# Xonik_Waveformer_v1_0.net
KiCad netlist of a schematic drawn in EAGLE
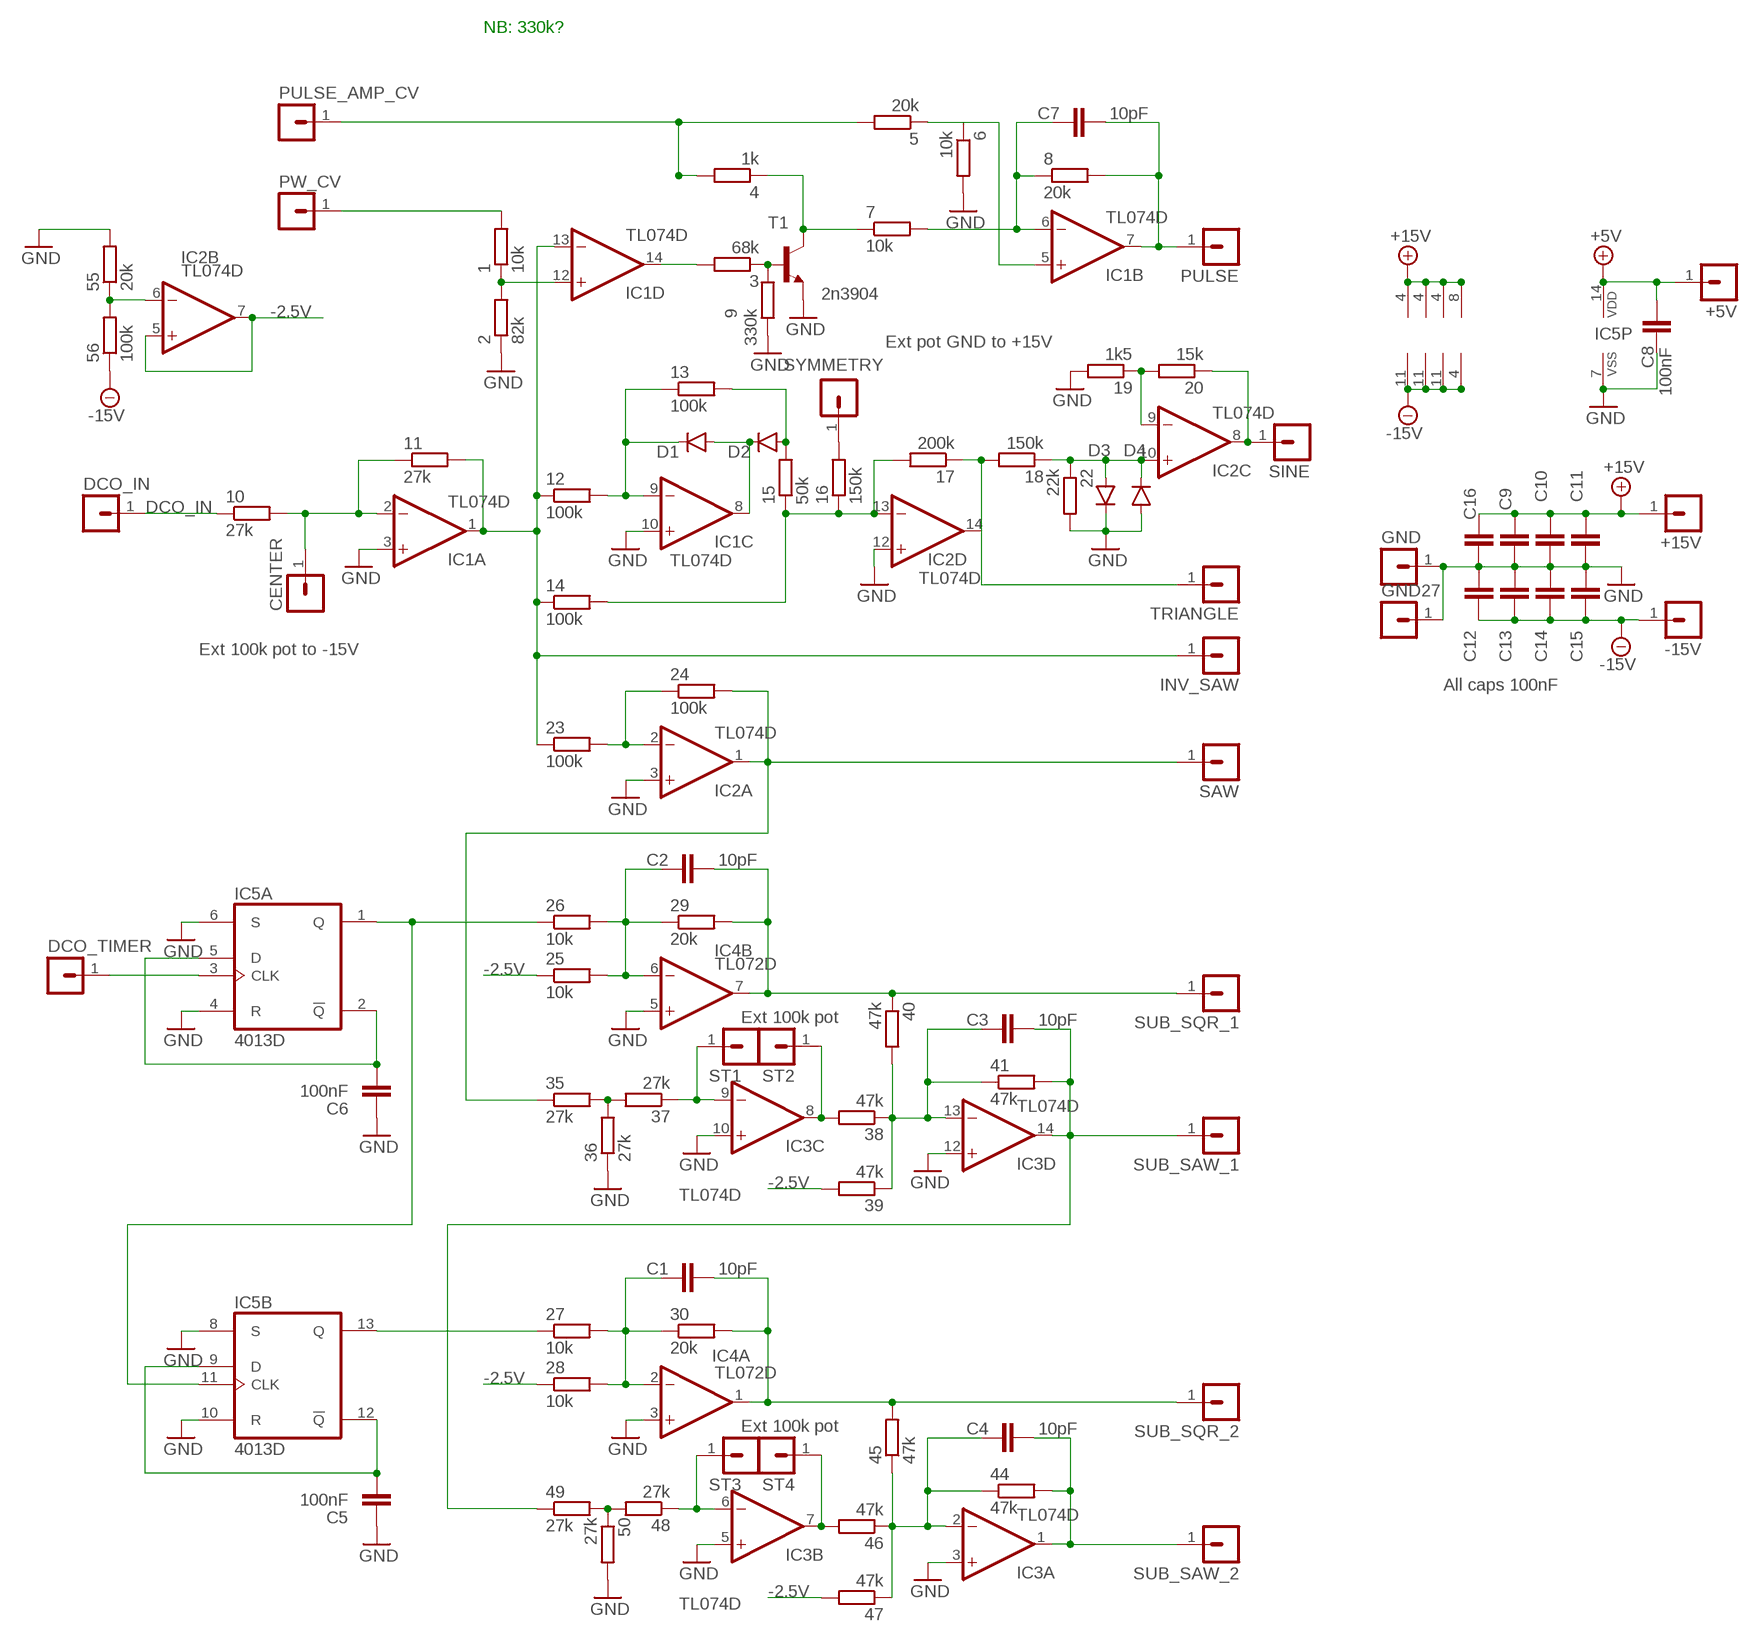
[diagram p0: schematic, sheet 1]

(export (version "E")
  (design (tool "Eeschema 10.0.6"))
  (components
    (comp (ref "+5V")
      (value "MA01-1JP")
      (footprint "eagle-import:SIP-PIN01-1J")
      (libsource (lib "eagle-import") (part "MA01-1JP"))
    )
    (comp (ref "+15V")
      (value "MA01-1JP")
      (footprint "eagle-import:SIP-PIN01-1J")
      (libsource (lib "eagle-import") (part "MA01-1JP"))
    )
    (comp (ref "-15V")
      (value "MA01-1JP")
      (footprint "eagle-import:SIP-PIN01-1J")
      (libsource (lib "eagle-import") (part "MA01-1JP"))
    )
    (comp (ref "1")
      (value "10k")
      (footprint "eagle-import:R0805")
      (libsource (lib "eagle-import") (part "R-EU_R0805"))
    )
    (comp (ref "2")
      (value "82k")
      (footprint "eagle-import:R0805")
      (libsource (lib "eagle-import") (part "R-EU_R0805"))
    )
    (comp (ref "3")
      (value "68k")
      (footprint "eagle-import:R0805")
      (libsource (lib "eagle-import") (part "R-EU_R0805"))
    )
    (comp (ref "4")
      (value "1k")
      (footprint "eagle-import:R0805")
      (libsource (lib "eagle-import") (part "R-EU_R0805"))
    )
    (comp (ref "5")
      (value "20k")
      (footprint "eagle-import:R0805")
      (libsource (lib "eagle-import") (part "R-EU_R0805"))
    )
    (comp (ref "6")
      (value "10k")
      (footprint "eagle-import:R0805")
      (libsource (lib "eagle-import") (part "R-EU_R0805"))
    )
    (comp (ref "7")
      (value "10k")
      (footprint "eagle-import:R0805")
      (libsource (lib "eagle-import") (part "R-EU_R0805"))
    )
    (comp (ref "8")
      (value "20k")
      (footprint "eagle-import:R0805")
      (libsource (lib "eagle-import") (part "R-EU_R0805"))
    )
    (comp (ref "9")
      (value "330k")
      (footprint "eagle-import:R0805")
      (libsource (lib "eagle-import") (part "R-EU_R0805"))
    )
    (comp (ref "10")
      (value "27k")
      (footprint "eagle-import:R0805")
      (libsource (lib "eagle-import") (part "R-EU_R0805"))
    )
    (comp (ref "11")
      (value "27k")
      (footprint "eagle-import:R0805")
      (libsource (lib "eagle-import") (part "R-EU_R0805"))
    )
    (comp (ref "12")
      (value "100k")
      (footprint "eagle-import:R0805")
      (libsource (lib "eagle-import") (part "R-EU_R0805"))
    )
    (comp (ref "13")
      (value "100k")
      (footprint "eagle-import:R0805")
      (libsource (lib "eagle-import") (part "R-EU_R0805"))
    )
    (comp (ref "14")
      (value "100k")
      (footprint "eagle-import:R0805")
      (libsource (lib "eagle-import") (part "R-EU_R0805"))
    )
    (comp (ref "15")
      (value "50k")
      (footprint "eagle-import:R0805")
      (libsource (lib "eagle-import") (part "R-EU_R0805"))
    )
    (comp (ref "16")
      (value "150k")
      (footprint "eagle-import:R0805")
      (libsource (lib "eagle-import") (part "R-EU_R0805"))
    )
    (comp (ref "17")
      (value "200k")
      (footprint "eagle-import:R0805")
      (libsource (lib "eagle-import") (part "R-EU_R0805"))
    )
    (comp (ref "18")
      (value "150k")
      (footprint "eagle-import:R0805")
      (libsource (lib "eagle-import") (part "R-EU_R0805"))
    )
    (comp (ref "19")
      (value "1k5")
      (footprint "eagle-import:R0805")
      (libsource (lib "eagle-import") (part "R-EU_R0805"))
    )
    (comp (ref "20")
      (value "15k")
      (footprint "eagle-import:R0805")
      (libsource (lib "eagle-import") (part "R-EU_R0805"))
    )
    (comp (ref "22")
      (value "22k")
      (footprint "eagle-import:R0805")
      (libsource (lib "eagle-import") (part "R-EU_R0805"))
    )
    (comp (ref "23")
      (value "100k")
      (footprint "eagle-import:R0805")
      (libsource (lib "eagle-import") (part "R-EU_R0805"))
    )
    (comp (ref "24")
      (value "100k")
      (footprint "eagle-import:R0805")
      (libsource (lib "eagle-import") (part "R-EU_R0805"))
    )
    (comp (ref "25")
      (value "10k")
      (footprint "eagle-import:R0805")
      (libsource (lib "eagle-import") (part "R-EU_R0805"))
    )
    (comp (ref "26")
      (value "10k")
      (footprint "eagle-import:R0805")
      (libsource (lib "eagle-import") (part "R-EU_R0805"))
    )
    (comp (ref "27")
      (value "10k")
      (footprint "eagle-import:R0805")
      (libsource (lib "eagle-import") (part "R-EU_R0805"))
    )
    (comp (ref "28")
      (value "10k")
      (footprint "eagle-import:R0805")
      (libsource (lib "eagle-import") (part "R-EU_R0805"))
    )
    (comp (ref "29")
      (value "20k")
      (footprint "eagle-import:R0805")
      (libsource (lib "eagle-import") (part "R-EU_R0805"))
    )
    (comp (ref "30")
      (value "20k")
      (footprint "eagle-import:R0805")
      (libsource (lib "eagle-import") (part "R-EU_R0805"))
    )
    (comp (ref "35")
      (value "27k")
      (footprint "eagle-import:R0805")
      (libsource (lib "eagle-import") (part "R-EU_R0805"))
    )
    (comp (ref "36")
      (value "27k")
      (footprint "eagle-import:R0805")
      (libsource (lib "eagle-import") (part "R-EU_R0805"))
    )
    (comp (ref "37")
      (value "27k")
      (footprint "eagle-import:R0805")
      (libsource (lib "eagle-import") (part "R-EU_R0805"))
    )
    (comp (ref "38")
      (value "47k")
      (footprint "eagle-import:R0805")
      (libsource (lib "eagle-import") (part "R-EU_R0805"))
    )
    (comp (ref "39")
      (value "47k")
      (footprint "eagle-import:R0805")
      (libsource (lib "eagle-import") (part "R-EU_R0805"))
    )
    (comp (ref "40")
      (value "47k")
      (footprint "eagle-import:R0805")
      (libsource (lib "eagle-import") (part "R-EU_R0805"))
    )
    (comp (ref "41")
      (value "47k")
      (footprint "eagle-import:R0805")
      (libsource (lib "eagle-import") (part "R-EU_R0805"))
    )
    (comp (ref "44")
      (value "47k")
      (footprint "eagle-import:R0805")
      (libsource (lib "eagle-import") (part "R-EU_R0805"))
    )
    (comp (ref "45")
      (value "47k")
      (footprint "eagle-import:R0805")
      (libsource (lib "eagle-import") (part "R-EU_R0805"))
    )
    (comp (ref "46")
      (value "47k")
      (footprint "eagle-import:R0805")
      (libsource (lib "eagle-import") (part "R-EU_R0805"))
    )
    (comp (ref "47")
      (value "47k")
      (footprint "eagle-import:R0805")
      (libsource (lib "eagle-import") (part "R-EU_R0805"))
    )
    (comp (ref "48")
      (value "27k")
      (footprint "eagle-import:R0805")
      (libsource (lib "eagle-import") (part "R-EU_R0805"))
    )
    (comp (ref "49")
      (value "27k")
      (footprint "eagle-import:R0805")
      (libsource (lib "eagle-import") (part "R-EU_R0805"))
    )
    (comp (ref "50")
      (value "27k")
      (footprint "eagle-import:R0805")
      (libsource (lib "eagle-import") (part "R-EU_R0805"))
    )
    (comp (ref "55")
      (value "20k")
      (footprint "eagle-import:R0805")
      (libsource (lib "eagle-import") (part "R-EU_R0805"))
    )
    (comp (ref "56")
      (value "100k")
      (footprint "eagle-import:R0805")
      (libsource (lib "eagle-import") (part "R-EU_R0805"))
    )
    (comp (ref "C1")
      (value "10pF")
      (footprint "eagle-import:C0805")
      (libsource (lib "eagle-import") (part "C-EUC0805"))
    )
    (comp (ref "C2")
      (value "10pF")
      (footprint "eagle-import:C0805")
      (libsource (lib "eagle-import") (part "C-EUC0805"))
    )
    (comp (ref "C3")
      (value "10pF")
      (footprint "eagle-import:C0805")
      (libsource (lib "eagle-import") (part "C-EUC0805"))
    )
    (comp (ref "C4")
      (value "10pF")
      (footprint "eagle-import:C0805")
      (libsource (lib "eagle-import") (part "C-EUC0805"))
    )
    (comp (ref "C5")
      (value "100nF")
      (footprint "eagle-import:C0805")
      (libsource (lib "eagle-import") (part "C-EUC0805"))
    )
    (comp (ref "C6")
      (value "100nF")
      (footprint "eagle-import:C0805")
      (libsource (lib "eagle-import") (part "C-EUC0805"))
    )
    (comp (ref "C7")
      (value "10pF")
      (footprint "eagle-import:C0805")
      (libsource (lib "eagle-import") (part "C-EUC0805"))
    )
    (comp (ref "C8")
      (value "100nF")
      (footprint "eagle-import:C0805")
      (libsource (lib "eagle-import") (part "C-EUC0805"))
    )
    (comp (ref "C9")
      (value "100nF")
      (footprint "eagle-import:C0603K")
      (libsource (lib "eagle-import") (part "C-EUC0603K"))
    )
    (comp (ref "C10")
      (value "100nF")
      (footprint "eagle-import:C0603K")
      (libsource (lib "eagle-import") (part "C-EUC0603K"))
    )
    (comp (ref "C11")
      (value "100nF")
      (footprint "eagle-import:C0603K")
      (libsource (lib "eagle-import") (part "C-EUC0603K"))
    )
    (comp (ref "C12")
      (value "100nF")
      (footprint "eagle-import:C0603K")
      (libsource (lib "eagle-import") (part "C-EUC0603K"))
    )
    (comp (ref "C13")
      (value "100nF")
      (footprint "eagle-import:C0603K")
      (libsource (lib "eagle-import") (part "C-EUC0603K"))
    )
    (comp (ref "C14")
      (value "100nF")
      (footprint "eagle-import:C0603K")
      (libsource (lib "eagle-import") (part "C-EUC0603K"))
    )
    (comp (ref "C15")
      (value "100nF")
      (footprint "eagle-import:C0603K")
      (libsource (lib "eagle-import") (part "C-EUC0603K"))
    )
    (comp (ref "C16")
      (value "100nF")
      (footprint "eagle-import:C0603K")
      (libsource (lib "eagle-import") (part "C-EUC0603K"))
    )
    (comp (ref "CENTER")
      (value "MA01-1JP")
      (footprint "eagle-import:SIP-PIN01-1J")
      (libsource (lib "eagle-import") (part "MA01-1JP"))
    )
    (comp (ref "D1")
      (value "1N41480805")
      (footprint "eagle-import:D0805-J")
      (libsource (lib "eagle-import") (part "1N41480805"))
    )
    (comp (ref "D2")
      (value "1N41480805")
      (footprint "eagle-import:D0805-J")
      (libsource (lib "eagle-import") (part "1N41480805"))
    )
    (comp (ref "D3")
      (value "1N41480805")
      (footprint "eagle-import:D0805-J")
      (libsource (lib "eagle-import") (part "1N41480805"))
    )
    (comp (ref "D4")
      (value "1N41480805")
      (footprint "eagle-import:D0805-J")
      (libsource (lib "eagle-import") (part "1N41480805"))
    )
    (comp (ref "DCO_IN")
      (value "MA01-1JP")
      (footprint "eagle-import:SIP-PIN01-1J")
      (libsource (lib "eagle-import") (part "MA01-1JP"))
    )
    (comp (ref "DCO_TIMER")
      (value "MA01-1JP")
      (footprint "eagle-import:SIP-PIN01-1J")
      (libsource (lib "eagle-import") (part "MA01-1JP"))
    )
    (comp (ref "GND")
      (value "MA01-1JP")
      (footprint "eagle-import:SIP-PIN01-1J")
      (libsource (lib "eagle-import") (part "MA01-1JP"))
    )
    (comp (ref "GND27")
      (value "MA01-1JP")
      (footprint "eagle-import:SIP-PIN01-1J")
      (libsource (lib "eagle-import") (part "MA01-1JP"))
    )
    (comp (ref "IC1")
      (value "TL074D")
      (footprint "eagle-import:SO14")
      (libsource (lib "eagle-import") (part "TL074D"))
    )
    (comp (ref "IC2")
      (value "TL074D")
      (footprint "eagle-import:SO14")
      (libsource (lib "eagle-import") (part "TL074D"))
    )
    (comp (ref "IC3")
      (value "TL074D")
      (footprint "eagle-import:SO14")
      (libsource (lib "eagle-import") (part "TL074D"))
    )
    (comp (ref "IC4")
      (value "TL072D")
      (footprint "eagle-import:SO08J")
      (libsource (lib "eagle-import") (part "TL072D"))
    )
    (comp (ref "IC5")
      (value "4013D")
      (footprint "eagle-import:SO14J")
      (libsource (lib "eagle-import") (part "4013D"))
    )
    (comp (ref "INV_SAW")
      (value "MA01-1JP")
      (footprint "eagle-import:SIP-PIN01-1J")
      (libsource (lib "eagle-import") (part "MA01-1JP"))
    )
    (comp (ref "PULSE")
      (value "MA01-1JP")
      (footprint "eagle-import:SIP-PIN01-1J")
      (libsource (lib "eagle-import") (part "MA01-1JP"))
    )
    (comp (ref "PULSE_AMP_CV")
      (value "MA01-1JP")
      (footprint "eagle-import:SIP-PIN01-1J")
      (libsource (lib "eagle-import") (part "MA01-1JP"))
    )
    (comp (ref "PW_CV")
      (value "MA01-1JP")
      (footprint "eagle-import:SIP-PIN01-1J")
      (libsource (lib "eagle-import") (part "MA01-1JP"))
    )
    (comp (ref "SAW")
      (value "MA01-1JP")
      (footprint "eagle-import:SIP-PIN01-1J")
      (libsource (lib "eagle-import") (part "MA01-1JP"))
    )
    (comp (ref "SINE")
      (value "MA01-1JP")
      (footprint "eagle-import:SIP-PIN01-1J")
      (libsource (lib "eagle-import") (part "MA01-1JP"))
    )
    (comp (ref "ST1")
      (value "MA01-1JP")
      (footprint "eagle-import:SIP-PIN01-1J")
      (libsource (lib "eagle-import") (part "MA01-1JP"))
    )
    (comp (ref "ST2")
      (value "MA01-1JP")
      (footprint "eagle-import:SIP-PIN01-1J")
      (libsource (lib "eagle-import") (part "MA01-1JP"))
    )
    (comp (ref "ST3")
      (value "MA01-1JP")
      (footprint "eagle-import:SIP-PIN01-1J")
      (libsource (lib "eagle-import") (part "MA01-1JP"))
    )
    (comp (ref "ST4")
      (value "MA01-1JP")
      (footprint "eagle-import:SIP-PIN01-1J")
      (libsource (lib "eagle-import") (part "MA01-1JP"))
    )
    (comp (ref "SUB_SAW_1")
      (value "MA01-1JP")
      (footprint "eagle-import:SIP-PIN01-1J")
      (libsource (lib "eagle-import") (part "MA01-1JP"))
    )
    (comp (ref "SUB_SAW_2")
      (value "MA01-1JP")
      (footprint "eagle-import:SIP-PIN01-1J")
      (libsource (lib "eagle-import") (part "MA01-1JP"))
    )
    (comp (ref "SUB_SQR_1")
      (value "MA01-1JP")
      (footprint "eagle-import:SIP-PIN01-1J")
      (libsource (lib "eagle-import") (part "MA01-1JP"))
    )
    (comp (ref "SUB_SQR_2")
      (value "MA01-1JP")
      (footprint "eagle-import:SIP-PIN01-1J")
      (libsource (lib "eagle-import") (part "MA01-1JP"))
    )
    (comp (ref "SYMMETRY")
      (value "MA01-1JP")
      (footprint "eagle-import:SIP-PIN01-1J")
      (libsource (lib "eagle-import") (part "MA01-1JP"))
    )
    (comp (ref "T1")
      (value "2n3904")
      (footprint "eagle-import:SOT23-BEC")
      (libsource (lib "eagle-import") (part "-NPN-SOT23-BECMMBT3904LT1"))
    )
    (comp (ref "TRIANGLE")
      (value "MA01-1JP")
      (footprint "eagle-import:SIP-PIN01-1J")
      (libsource (lib "eagle-import") (part "MA01-1JP"))
    )
  )
  (nets
    (net (code "1") (name "+5V") (class "Default")
      (node (ref "+5V") (pin "1") (pinfunction "1_1") (pintype "passive"))
      (node (ref "C8") (pin "2") (pinfunction "2_2") (pintype "passive"))
      (node (ref "IC5") (pin "14") (pinfunction "VDD_14") (pintype "power_in"))
    )
    (net (code "2") (name "+15V") (class "Default")
      (node (ref "+15V") (pin "1") (pinfunction "1_1") (pintype "passive"))
      (node (ref "C10") (pin "2") (pinfunction "2_2") (pintype "passive"))
      (node (ref "C11") (pin "2") (pinfunction "2_2") (pintype "passive"))
      (node (ref "C16") (pin "2") (pinfunction "2_2") (pintype "passive"))
      (node (ref "C9") (pin "2") (pinfunction "2_2") (pintype "passive"))
      (node (ref "IC1") (pin "4") (pinfunction "V+_4") (pintype "power_in"))
      (node (ref "IC2") (pin "4") (pinfunction "V+_4") (pintype "power_in"))
      (node (ref "IC3") (pin "4") (pinfunction "V+_4") (pintype "power_in"))
      (node (ref "IC4") (pin "8") (pinfunction "V+_8") (pintype "power_in"))
    )
    (net (code "3") (name "-15V") (class "Default")
      (node (ref "-15V") (pin "1") (pinfunction "1_1") (pintype "passive"))
      (node (ref "56") (pin "1") (pinfunction "1_1") (pintype "passive"))
      (node (ref "C12") (pin "1") (pinfunction "1_1") (pintype "passive"))
      (node (ref "C13") (pin "1") (pinfunction "1_1") (pintype "passive"))
      (node (ref "C14") (pin "1") (pinfunction "1_1") (pintype "passive"))
      (node (ref "C15") (pin "1") (pinfunction "1_1") (pintype "passive"))
      (node (ref "IC1") (pin "11") (pinfunction "V-_11") (pintype "power_in"))
      (node (ref "IC2") (pin "11") (pinfunction "V-_11") (pintype "power_in"))
      (node (ref "IC3") (pin "11") (pinfunction "V-_11") (pintype "power_in"))
      (node (ref "IC4") (pin "4") (pinfunction "V-_4") (pintype "power_in"))
    )
    (net (code "4") (name "/-2.5V") (class "Default")
      (node (ref "25") (pin "1") (pinfunction "1_1") (pintype "passive"))
      (node (ref "28") (pin "1") (pinfunction "1_1") (pintype "passive"))
      (node (ref "39") (pin "2") (pinfunction "2_2") (pintype "passive"))
      (node (ref "47") (pin "2") (pinfunction "2_2") (pintype "passive"))
      (node (ref "IC2") (pin "5") (pinfunction "+IN_5") (pintype "input"))
      (node (ref "IC2") (pin "7") (pinfunction "OUT_7") (pintype "output"))
    )
    (net (code "5") (name "/DCO_IN") (class "Default")
      (node (ref "10") (pin "1") (pinfunction "1_1") (pintype "passive"))
      (node (ref "DCO_IN") (pin "1") (pinfunction "1_1") (pintype "passive"))
    )
    (net (code "6") (name "GND") (class "Default")
      (node (ref "19") (pin "2") (pinfunction "2_2") (pintype "passive"))
      (node (ref "2") (pin "1") (pinfunction "1_1") (pintype "passive"))
      (node (ref "22") (pin "2") (pinfunction "2_2") (pintype "passive"))
      (node (ref "36") (pin "1") (pinfunction "1_1") (pintype "passive"))
      (node (ref "50") (pin "2") (pinfunction "2_2") (pintype "passive"))
      (node (ref "55") (pin "2") (pinfunction "2_2") (pintype "passive"))
      (node (ref "6") (pin "2") (pinfunction "2_2") (pintype "passive"))
      (node (ref "9") (pin "2") (pinfunction "2_2") (pintype "passive"))
      (node (ref "C10") (pin "1") (pinfunction "1_1") (pintype "passive"))
      (node (ref "C11") (pin "1") (pinfunction "1_1") (pintype "passive"))
      (node (ref "C12") (pin "2") (pinfunction "2_2") (pintype "passive"))
      (node (ref "C13") (pin "2") (pinfunction "2_2") (pintype "passive"))
      (node (ref "C14") (pin "2") (pinfunction "2_2") (pintype "passive"))
      (node (ref "C15") (pin "2") (pinfunction "2_2") (pintype "passive"))
      (node (ref "C16") (pin "1") (pinfunction "1_1") (pintype "passive"))
      (node (ref "C5") (pin "1") (pinfunction "1_1") (pintype "passive"))
      (node (ref "C6") (pin "1") (pinfunction "1_1") (pintype "passive"))
      (node (ref "C8") (pin "1") (pinfunction "1_1") (pintype "passive"))
      (node (ref "C9") (pin "1") (pinfunction "1_1") (pintype "passive"))
      (node (ref "D3") (pin "C") (pinfunction "C_C") (pintype "passive"))
      (node (ref "D4") (pin "A") (pinfunction "A_A") (pintype "passive"))
      (node (ref "GND") (pin "1") (pinfunction "1_1") (pintype "passive"))
      (node (ref "GND27") (pin "1") (pinfunction "1_1") (pintype "passive"))
      (node (ref "IC1") (pin "10") (pinfunction "+IN_10") (pintype "input"))
      (node (ref "IC1") (pin "3") (pinfunction "+IN_3") (pintype "input"))
      (node (ref "IC2") (pin "12") (pinfunction "+IN_12") (pintype "input"))
      (node (ref "IC2") (pin "3") (pinfunction "+IN_3") (pintype "input"))
      (node (ref "IC3") (pin "10") (pinfunction "+IN_10") (pintype "input"))
      (node (ref "IC3") (pin "12") (pinfunction "+IN_12") (pintype "input"))
      (node (ref "IC3") (pin "3") (pinfunction "+IN_3") (pintype "input"))
      (node (ref "IC3") (pin "5") (pinfunction "+IN_5") (pintype "input"))
      (node (ref "IC4") (pin "3") (pinfunction "+IN_3") (pintype "input"))
      (node (ref "IC4") (pin "5") (pinfunction "+IN_5") (pintype "input"))
      (node (ref "IC5") (pin "10") (pinfunction "R_10") (pintype "input"))
      (node (ref "IC5") (pin "4") (pinfunction "R_4") (pintype "input"))
      (node (ref "IC5") (pin "6") (pinfunction "S_6") (pintype "input"))
      (node (ref "IC5") (pin "7") (pinfunction "VSS_7") (pintype "power_in"))
      (node (ref "IC5") (pin "8") (pinfunction "S_8") (pintype "input"))
      (node (ref "T1") (pin "E") (pinfunction "E_E") (pintype "passive"))
    )
    (net (code "7") (name "Net-(1-Pad2)") (class "Default")
      (node (ref "1") (pin "2") (pinfunction "2_2") (pintype "passive"))
      (node (ref "PW_CV") (pin "1") (pinfunction "1_1") (pintype "passive"))
    )
    (net (code "8") (name "Net-(3-Pad1)") (class "Default")
      (node (ref "3") (pin "1") (pinfunction "1_1") (pintype "passive"))
      (node (ref "9") (pin "1") (pinfunction "1_1") (pintype "passive"))
      (node (ref "T1") (pin "B") (pinfunction "B_B") (pintype "passive"))
    )
    (net (code "9") (name "Net-(4-Pad1)") (class "Default")
      (node (ref "4") (pin "1") (pinfunction "1_1") (pintype "passive"))
      (node (ref "7") (pin "1") (pinfunction "1_1") (pintype "passive"))
      (node (ref "T1") (pin "C") (pinfunction "C_C") (pintype "passive"))
    )
    (net (code "10") (name "Net-(4-Pad2)") (class "Default")
      (node (ref "4") (pin "2") (pinfunction "2_2") (pintype "passive"))
      (node (ref "5") (pin "2") (pinfunction "2_2") (pintype "passive"))
      (node (ref "PULSE_AMP_CV") (pin "1") (pinfunction "1_1") (pintype "passive"))
    )
    (net (code "11") (name "Net-(13-Pad2)") (class "Default")
      (node (ref "13") (pin "2") (pinfunction "2_2") (pintype "passive"))
      (node (ref "15") (pin "2") (pinfunction "2_2") (pintype "passive"))
      (node (ref "D2") (pin "A") (pinfunction "A_A") (pintype "passive"))
    )
    (net (code "12") (name "Net-(16-Pad2)") (class "Default")
      (node (ref "16") (pin "2") (pinfunction "2_2") (pintype "passive"))
      (node (ref "SYMMETRY") (pin "1") (pinfunction "1_1") (pintype "passive"))
    )
    (net (code "13") (name "Net-(35-Pad2)") (class "Default")
      (node (ref "35") (pin "2") (pinfunction "2_2") (pintype "passive"))
      (node (ref "36") (pin "2") (pinfunction "2_2") (pintype "passive"))
      (node (ref "37") (pin "2") (pinfunction "2_2") (pintype "passive"))
    )
    (net (code "14") (name "Net-(48-Pad2)") (class "Default")
      (node (ref "48") (pin "2") (pinfunction "2_2") (pintype "passive"))
      (node (ref "49") (pin "2") (pinfunction "2_2") (pintype "passive"))
      (node (ref "50") (pin "1") (pinfunction "1_1") (pintype "passive"))
    )
    (net (code "15") (name "Net-(IC1A--IN)") (class "Default")
      (node (ref "10") (pin "2") (pinfunction "2_2") (pintype "passive"))
      (node (ref "11") (pin "1") (pinfunction "1_1") (pintype "passive"))
      (node (ref "CENTER") (pin "1") (pinfunction "1_1") (pintype "passive"))
      (node (ref "IC1") (pin "2") (pinfunction "-IN_2") (pintype "input"))
    )
    (net (code "16") (name "Net-(IC1A-OUT)") (class "Default")
      (node (ref "11") (pin "2") (pinfunction "2_2") (pintype "passive"))
      (node (ref "12") (pin "1") (pinfunction "1_1") (pintype "passive"))
      (node (ref "14") (pin "1") (pinfunction "1_1") (pintype "passive"))
      (node (ref "23") (pin "1") (pinfunction "1_1") (pintype "passive"))
      (node (ref "IC1") (pin "1") (pinfunction "OUT_1") (pintype "output"))
      (node (ref "IC1") (pin "13") (pinfunction "-IN_13") (pintype "input"))
      (node (ref "INV_SAW") (pin "1") (pinfunction "1_1") (pintype "passive"))
    )
    (net (code "17") (name "Net-(IC1B-+IN)") (class "Default")
      (node (ref "5") (pin "1") (pinfunction "1_1") (pintype "passive"))
      (node (ref "6") (pin "1") (pinfunction "1_1") (pintype "passive"))
      (node (ref "IC1") (pin "5") (pinfunction "+IN_5") (pintype "input"))
    )
    (net (code "18") (name "Net-(IC1B--IN)") (class "Default")
      (node (ref "7") (pin "2") (pinfunction "2_2") (pintype "passive"))
      (node (ref "8") (pin "1") (pinfunction "1_1") (pintype "passive"))
      (node (ref "C7") (pin "1") (pinfunction "1_1") (pintype "passive"))
      (node (ref "IC1") (pin "6") (pinfunction "-IN_6") (pintype "input"))
    )
    (net (code "19") (name "Net-(IC1B-OUT)") (class "Default")
      (node (ref "8") (pin "2") (pinfunction "2_2") (pintype "passive"))
      (node (ref "C7") (pin "2") (pinfunction "2_2") (pintype "passive"))
      (node (ref "IC1") (pin "7") (pinfunction "OUT_7") (pintype "output"))
      (node (ref "PULSE") (pin "1") (pinfunction "1_1") (pintype "passive"))
    )
    (net (code "20") (name "Net-(IC1C--IN)") (class "Default")
      (node (ref "12") (pin "2") (pinfunction "2_2") (pintype "passive"))
      (node (ref "13") (pin "1") (pinfunction "1_1") (pintype "passive"))
      (node (ref "D1") (pin "C") (pinfunction "C_C") (pintype "passive"))
      (node (ref "IC1") (pin "9") (pinfunction "-IN_9") (pintype "input"))
    )
    (net (code "21") (name "Net-(IC1C-OUT)") (class "Default")
      (node (ref "D1") (pin "A") (pinfunction "A_A") (pintype "passive"))
      (node (ref "D2") (pin "C") (pinfunction "C_C") (pintype "passive"))
      (node (ref "IC1") (pin "8") (pinfunction "OUT_8") (pintype "output"))
    )
    (net (code "22") (name "Net-(IC1D-+IN)") (class "Default")
      (node (ref "1") (pin "1") (pinfunction "1_1") (pintype "passive"))
      (node (ref "2") (pin "2") (pinfunction "2_2") (pintype "passive"))
      (node (ref "IC1") (pin "12") (pinfunction "+IN_12") (pintype "input"))
    )
    (net (code "23") (name "Net-(IC1D-OUT)") (class "Default")
      (node (ref "3") (pin "2") (pinfunction "2_2") (pintype "passive"))
      (node (ref "IC1") (pin "14") (pinfunction "OUT_14") (pintype "output"))
    )
    (net (code "24") (name "Net-(IC2A--IN)") (class "Default")
      (node (ref "23") (pin "2") (pinfunction "2_2") (pintype "passive"))
      (node (ref "24") (pin "1") (pinfunction "1_1") (pintype "passive"))
      (node (ref "IC2") (pin "2") (pinfunction "-IN_2") (pintype "input"))
    )
    (net (code "25") (name "Net-(IC2A-OUT)") (class "Default")
      (node (ref "24") (pin "2") (pinfunction "2_2") (pintype "passive"))
      (node (ref "35") (pin "1") (pinfunction "1_1") (pintype "passive"))
      (node (ref "IC2") (pin "1") (pinfunction "OUT_1") (pintype "output"))
      (node (ref "SAW") (pin "1") (pinfunction "1_1") (pintype "passive"))
    )
    (net (code "26") (name "Net-(IC2B--IN)") (class "Default")
      (node (ref "55") (pin "1") (pinfunction "1_1") (pintype "passive"))
      (node (ref "56") (pin "2") (pinfunction "2_2") (pintype "passive"))
      (node (ref "IC2") (pin "6") (pinfunction "-IN_6") (pintype "input"))
    )
    (net (code "27") (name "Net-(IC2C-+IN)") (class "Default")
      (node (ref "18") (pin "1") (pinfunction "1_1") (pintype "passive"))
      (node (ref "22") (pin "1") (pinfunction "1_1") (pintype "passive"))
      (node (ref "D3") (pin "A") (pinfunction "A_A") (pintype "passive"))
      (node (ref "D4") (pin "C") (pinfunction "C_C") (pintype "passive"))
      (node (ref "IC2") (pin "10") (pinfunction "+IN_10") (pintype "input"))
    )
    (net (code "28") (name "Net-(IC2C--IN)") (class "Default")
      (node (ref "19") (pin "1") (pinfunction "1_1") (pintype "passive"))
      (node (ref "20") (pin "2") (pinfunction "2_2") (pintype "passive"))
      (node (ref "IC2") (pin "9") (pinfunction "-IN_9") (pintype "input"))
    )
    (net (code "29") (name "Net-(IC2C-OUT)") (class "Default")
      (node (ref "20") (pin "1") (pinfunction "1_1") (pintype "passive"))
      (node (ref "IC2") (pin "8") (pinfunction "OUT_8") (pintype "output"))
      (node (ref "SINE") (pin "1") (pinfunction "1_1") (pintype "passive"))
    )
    (net (code "30") (name "Net-(IC2D--IN)") (class "Default")
      (node (ref "14") (pin "2") (pinfunction "2_2") (pintype "passive"))
      (node (ref "15") (pin "1") (pinfunction "1_1") (pintype "passive"))
      (node (ref "16") (pin "1") (pinfunction "1_1") (pintype "passive"))
      (node (ref "17") (pin "2") (pinfunction "2_2") (pintype "passive"))
      (node (ref "IC2") (pin "13") (pinfunction "-IN_13") (pintype "input"))
    )
    (net (code "31") (name "Net-(IC2D-OUT)") (class "Default")
      (node (ref "17") (pin "1") (pinfunction "1_1") (pintype "passive"))
      (node (ref "18") (pin "2") (pinfunction "2_2") (pintype "passive"))
      (node (ref "IC2") (pin "14") (pinfunction "OUT_14") (pintype "output"))
      (node (ref "TRIANGLE") (pin "1") (pinfunction "1_1") (pintype "passive"))
    )
    (net (code "32") (name "Net-(IC3A--IN)") (class "Default")
      (node (ref "44") (pin "1") (pinfunction "1_1") (pintype "passive"))
      (node (ref "45") (pin "1") (pinfunction "1_1") (pintype "passive"))
      (node (ref "46") (pin "1") (pinfunction "1_1") (pintype "passive"))
      (node (ref "47") (pin "1") (pinfunction "1_1") (pintype "passive"))
      (node (ref "C4") (pin "1") (pinfunction "1_1") (pintype "passive"))
      (node (ref "IC3") (pin "2") (pinfunction "-IN_2") (pintype "input"))
    )
    (net (code "33") (name "Net-(IC3A-OUT)") (class "Default")
      (node (ref "44") (pin "2") (pinfunction "2_2") (pintype "passive"))
      (node (ref "C4") (pin "2") (pinfunction "2_2") (pintype "passive"))
      (node (ref "IC3") (pin "1") (pinfunction "OUT_1") (pintype "output"))
      (node (ref "SUB_SAW_2") (pin "1") (pinfunction "1_1") (pintype "passive"))
    )
    (net (code "34") (name "Net-(IC3B--IN)") (class "Default")
      (node (ref "48") (pin "1") (pinfunction "1_1") (pintype "passive"))
      (node (ref "IC3") (pin "6") (pinfunction "-IN_6") (pintype "input"))
      (node (ref "ST3") (pin "1") (pinfunction "1_1") (pintype "passive"))
    )
    (net (code "35") (name "Net-(IC3B-OUT)") (class "Default")
      (node (ref "46") (pin "2") (pinfunction "2_2") (pintype "passive"))
      (node (ref "IC3") (pin "7") (pinfunction "OUT_7") (pintype "output"))
      (node (ref "ST4") (pin "1") (pinfunction "1_1") (pintype "passive"))
    )
    (net (code "36") (name "Net-(IC3C--IN)") (class "Default")
      (node (ref "37") (pin "1") (pinfunction "1_1") (pintype "passive"))
      (node (ref "IC3") (pin "9") (pinfunction "-IN_9") (pintype "input"))
      (node (ref "ST1") (pin "1") (pinfunction "1_1") (pintype "passive"))
    )
    (net (code "37") (name "Net-(IC3C-OUT)") (class "Default")
      (node (ref "38") (pin "2") (pinfunction "2_2") (pintype "passive"))
      (node (ref "IC3") (pin "8") (pinfunction "OUT_8") (pintype "output"))
      (node (ref "ST2") (pin "1") (pinfunction "1_1") (pintype "passive"))
    )
    (net (code "38") (name "Net-(IC3D--IN)") (class "Default")
      (node (ref "38") (pin "1") (pinfunction "1_1") (pintype "passive"))
      (node (ref "39") (pin "1") (pinfunction "1_1") (pintype "passive"))
      (node (ref "40") (pin "2") (pinfunction "2_2") (pintype "passive"))
      (node (ref "41") (pin "1") (pinfunction "1_1") (pintype "passive"))
      (node (ref "C3") (pin "1") (pinfunction "1_1") (pintype "passive"))
      (node (ref "IC3") (pin "13") (pinfunction "-IN_13") (pintype "input"))
    )
    (net (code "39") (name "Net-(IC3D-OUT)") (class "Default")
      (node (ref "41") (pin "2") (pinfunction "2_2") (pintype "passive"))
      (node (ref "49") (pin "1") (pinfunction "1_1") (pintype "passive"))
      (node (ref "C3") (pin "2") (pinfunction "2_2") (pintype "passive"))
      (node (ref "IC3") (pin "14") (pinfunction "OUT_14") (pintype "output"))
      (node (ref "SUB_SAW_1") (pin "1") (pinfunction "1_1") (pintype "passive"))
    )
    (net (code "40") (name "Net-(IC4A--IN)") (class "Default")
      (node (ref "27") (pin "2") (pinfunction "2_2") (pintype "passive"))
      (node (ref "28") (pin "2") (pinfunction "2_2") (pintype "passive"))
      (node (ref "30") (pin "1") (pinfunction "1_1") (pintype "passive"))
      (node (ref "C1") (pin "1") (pinfunction "1_1") (pintype "passive"))
      (node (ref "IC4") (pin "2") (pinfunction "-IN_2") (pintype "input"))
    )
    (net (code "41") (name "Net-(IC4A-OUT)") (class "Default")
      (node (ref "30") (pin "2") (pinfunction "2_2") (pintype "passive"))
      (node (ref "45") (pin "2") (pinfunction "2_2") (pintype "passive"))
      (node (ref "C1") (pin "2") (pinfunction "2_2") (pintype "passive"))
      (node (ref "IC4") (pin "1") (pinfunction "OUT_1") (pintype "output"))
      (node (ref "SUB_SQR_2") (pin "1") (pinfunction "1_1") (pintype "passive"))
    )
    (net (code "42") (name "Net-(IC4B--IN)") (class "Default")
      (node (ref "25") (pin "2") (pinfunction "2_2") (pintype "passive"))
      (node (ref "26") (pin "2") (pinfunction "2_2") (pintype "passive"))
      (node (ref "29") (pin "1") (pinfunction "1_1") (pintype "passive"))
      (node (ref "C2") (pin "1") (pinfunction "1_1") (pintype "passive"))
      (node (ref "IC4") (pin "6") (pinfunction "-IN_6") (pintype "input"))
    )
    (net (code "43") (name "Net-(IC4B-OUT)") (class "Default")
      (node (ref "29") (pin "2") (pinfunction "2_2") (pintype "passive"))
      (node (ref "40") (pin "1") (pinfunction "1_1") (pintype "passive"))
      (node (ref "C2") (pin "2") (pinfunction "2_2") (pintype "passive"))
      (node (ref "IC4") (pin "7") (pinfunction "OUT_7") (pintype "output"))
      (node (ref "SUB_SQR_1") (pin "1") (pinfunction "1_1") (pintype "passive"))
    )
    (net (code "44") (name "Net-(IC5A-CLK)") (class "Default")
      (node (ref "DCO_TIMER") (pin "1") (pinfunction "1_1") (pintype "passive"))
      (node (ref "IC5") (pin "3") (pinfunction "CLK_3") (pintype "input"))
    )
    (net (code "45") (name "Net-(IC5A-D)") (class "Default")
      (node (ref "C6") (pin "2") (pinfunction "2_2") (pintype "passive"))
      (node (ref "IC5") (pin "2") (pinfunction "~{Q}_2") (pintype "output"))
      (node (ref "IC5") (pin "5") (pinfunction "D_5") (pintype "input"))
    )
    (net (code "46") (name "Net-(IC5A-Q)") (class "Default")
      (node (ref "26") (pin "1") (pinfunction "1_1") (pintype "passive"))
      (node (ref "IC5") (pin "1") (pinfunction "Q_1") (pintype "output"))
      (node (ref "IC5") (pin "11") (pinfunction "CLK_11") (pintype "input"))
    )
    (net (code "47") (name "Net-(IC5B-D)") (class "Default")
      (node (ref "C5") (pin "2") (pinfunction "2_2") (pintype "passive"))
      (node (ref "IC5") (pin "12") (pinfunction "~{Q}_12") (pintype "output"))
      (node (ref "IC5") (pin "9") (pinfunction "D_9") (pintype "input"))
    )
    (net (code "48") (name "Net-(IC5B-Q)") (class "Default")
      (node (ref "27") (pin "1") (pinfunction "1_1") (pintype "passive"))
      (node (ref "IC5") (pin "13") (pinfunction "Q_13") (pintype "output"))
    )
  )
)
